# USB_Type-C_Test.net
KiCad netlist of a schematic drawn in EAGLE
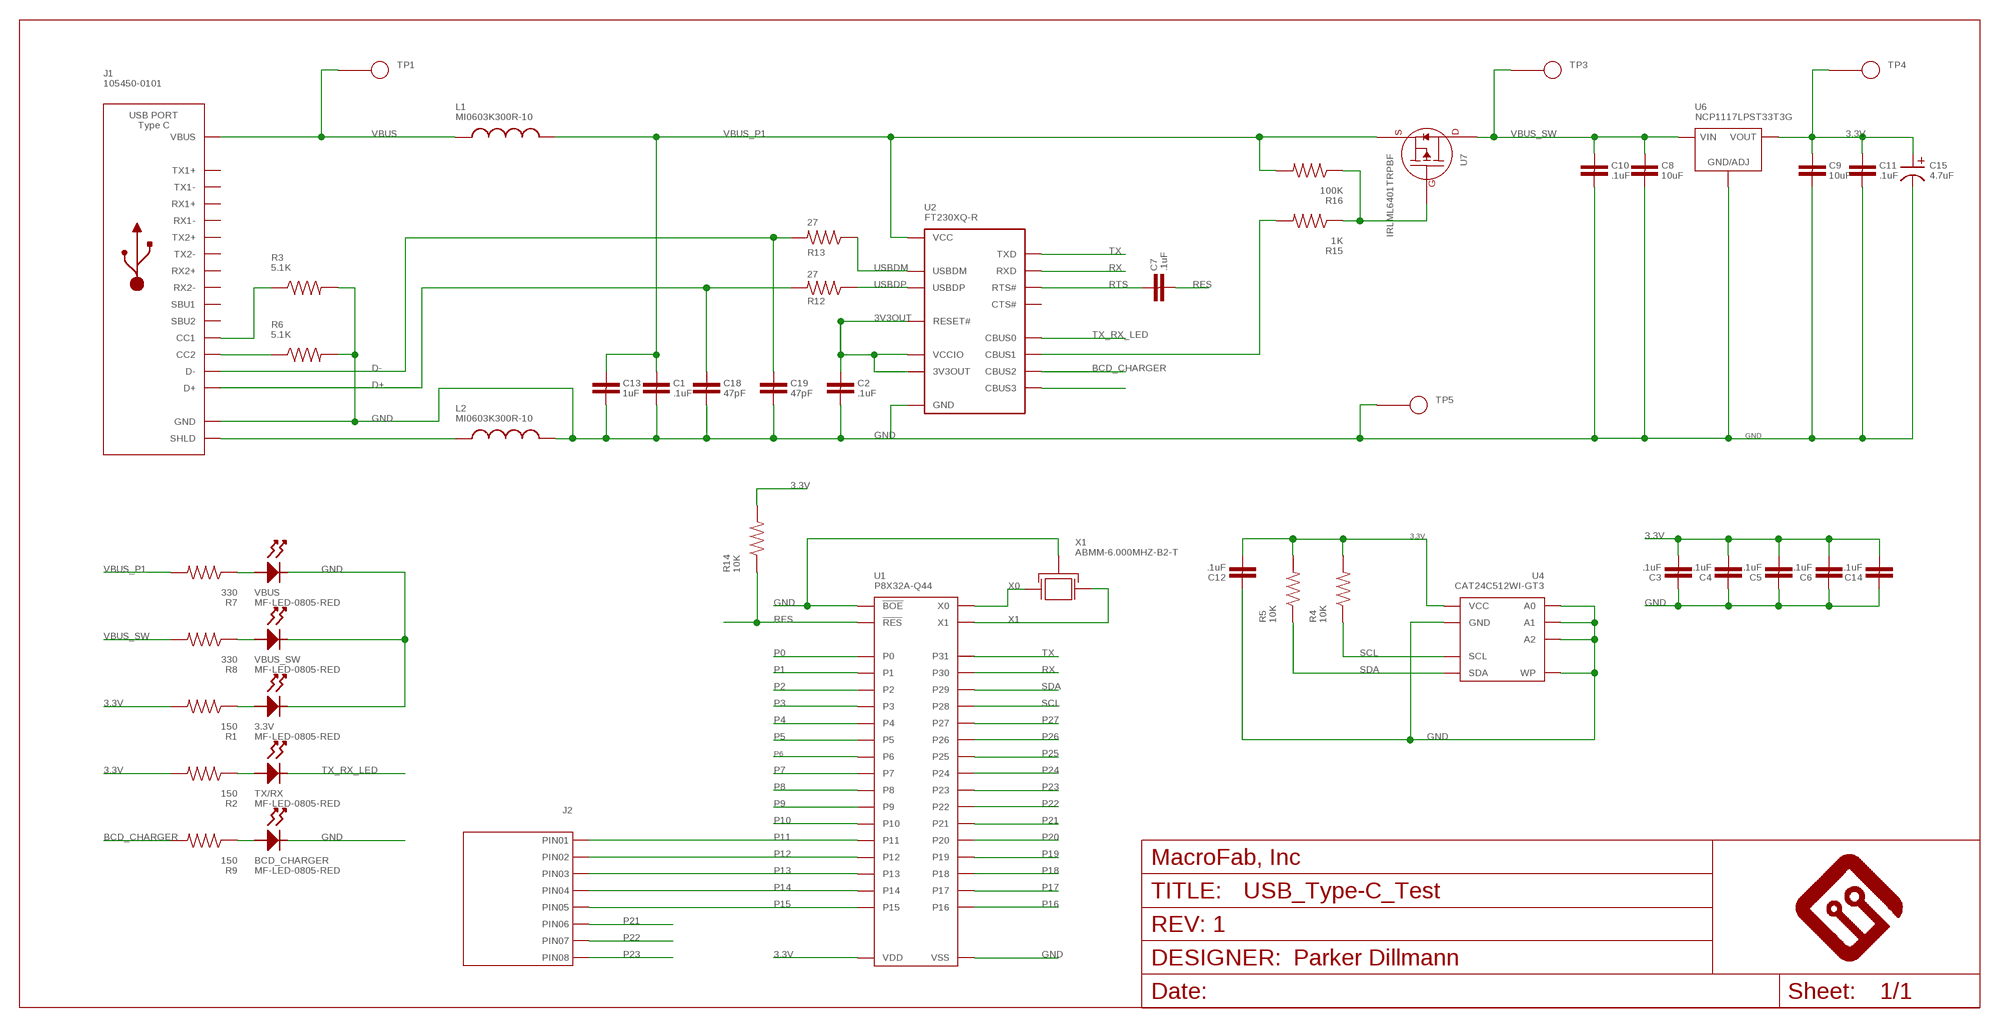
[diagram p0: schematic, sheet 1]

(export (version "E")
  (design (tool "Eeschema 10.0.6"))
  (components
    (comp (ref "3.3V")
      (value "MF-LED-0805-RED")
      (footprint "eagle-import:LED_0805")
      (libsource (lib "eagle-import") (part "LED_SINGLE_0805"))
    )
    (comp (ref "BCD_CHARGER")
      (value "MF-LED-0805-RED")
      (footprint "eagle-import:LED_0805")
      (libsource (lib "eagle-import") (part "LED_SINGLE_0805"))
    )
    (comp (ref "C1")
      (value ".1uF")
      (footprint "eagle-import:0603")
      (libsource (lib "eagle-import") (part "CAPACITOR_NON_POLAR_0603"))
    )
    (comp (ref "C2")
      (value ".1uF")
      (footprint "eagle-import:0603")
      (libsource (lib "eagle-import") (part "CAPACITOR_NON_POLAR_0603"))
    )
    (comp (ref "C3")
      (value ".1uF")
      (footprint "eagle-import:0603")
      (libsource (lib "eagle-import") (part "CAPACITOR_NON_POLAR_0603"))
    )
    (comp (ref "C4")
      (value ".1uF")
      (footprint "eagle-import:0603")
      (libsource (lib "eagle-import") (part "CAPACITOR_NON_POLAR_0603"))
    )
    (comp (ref "C5")
      (value ".1uF")
      (footprint "eagle-import:0603")
      (libsource (lib "eagle-import") (part "CAPACITOR_NON_POLAR_0603"))
    )
    (comp (ref "C6")
      (value ".1uF")
      (footprint "eagle-import:0603")
      (libsource (lib "eagle-import") (part "CAPACITOR_NON_POLAR_0603"))
    )
    (comp (ref "C7")
      (value ".1uF")
      (footprint "eagle-import:0603")
      (libsource (lib "eagle-import") (part "CAPACITOR_NON_POLAR_0603"))
    )
    (comp (ref "C8")
      (value "10uF")
      (footprint "eagle-import:1206")
      (libsource (lib "eagle-import") (part "CAPACITOR_NON_POLAR_1206"))
    )
    (comp (ref "C9")
      (value "10uF")
      (footprint "eagle-import:1206")
      (libsource (lib "eagle-import") (part "CAPACITOR_NON_POLAR_1206"))
    )
    (comp (ref "C10")
      (value ".1uF")
      (footprint "eagle-import:0603")
      (libsource (lib "eagle-import") (part "CAPACITOR_NON_POLAR_0603"))
    )
    (comp (ref "C11")
      (value ".1uF")
      (footprint "eagle-import:0603")
      (libsource (lib "eagle-import") (part "CAPACITOR_NON_POLAR_0603"))
    )
    (comp (ref "C12")
      (value ".1uF")
      (footprint "eagle-import:0603")
      (libsource (lib "eagle-import") (part "CAPACITOR_NON_POLAR_0603"))
    )
    (comp (ref "C13")
      (value "1uF")
      (footprint "eagle-import:0603")
      (libsource (lib "eagle-import") (part "CAPACITOR_NON_POLAR_0603"))
    )
    (comp (ref "C14")
      (value ".1uF")
      (footprint "eagle-import:0603")
      (libsource (lib "eagle-import") (part "CAPACITOR_NON_POLAR_0603"))
    )
    (comp (ref "C15")
      (value "4.7uF")
      (footprint "eagle-import:5MM_CAP_SMD")
      (libsource (lib "eagle-import") (part "CAPACITOR_POLARIZED_5MM_SMD"))
    )
    (comp (ref "C18")
      (value "47pF")
      (footprint "eagle-import:0603")
      (libsource (lib "eagle-import") (part "CAPACITOR_NON_POLAR_0603"))
    )
    (comp (ref "C19")
      (value "47pF")
      (footprint "eagle-import:0603")
      (libsource (lib "eagle-import") (part "CAPACITOR_NON_POLAR_0603"))
    )
    (comp (ref "FRAME1")
      (value "MF_FRAMEDEFAULT")
      (footprint "eagle-import:MF_FRAME_DEFAULT")
      (fields
        (field (name "HOUSEPART") "0")
        (field (name "DNAME") "Parker Dillmann")
        (field (name "REVNUM") "REV: 1")
      )
      (libsource (lib "eagle-import") (part "MF_FRAMEDEFAULT"))
    )
    (comp (ref "J1")
      (value "105450-0101")
      (footprint "eagle-import:105450-0101")
      (fields (field (name "MPN") "105450-0101"))
      (libsource (lib "eagle-import") (part "USB_TYPE-C_105450-0101"))
    )
    (comp (ref "J2")
      (value "CON_01X08_2.54MM_PIN_HEADER")
      (footprint "eagle-import:2.54MM_01X08_PIN_HEADER")
      (libsource (lib "eagle-import") (part "CON_01X08_2.54MM_PIN_HEADER"))
    )
    (comp (ref "L1")
      (value "MI0603K300R-10")
      (footprint "eagle-import:0603")
      (libsource (lib "eagle-import") (part "INDUCTOR_0603"))
    )
    (comp (ref "L2")
      (value "MI0603K300R-10")
      (footprint "eagle-import:0603")
      (libsource (lib "eagle-import") (part "INDUCTOR_0603"))
    )
    (comp (ref "R1")
      (value "150")
      (footprint "eagle-import:0603")
      (libsource (lib "eagle-import") (part "RESISTOR_0603"))
    )
    (comp (ref "R2")
      (value "150")
      (footprint "eagle-import:0603")
      (libsource (lib "eagle-import") (part "RESISTOR_0603"))
    )
    (comp (ref "R3")
      (value "5.1K")
      (footprint "eagle-import:0603")
      (libsource (lib "eagle-import") (part "RESISTOR_0603"))
    )
    (comp (ref "R4")
      (value "10K")
      (footprint "eagle-import:0603")
      (libsource (lib "eagle-import") (part "RESISTOR_0603"))
    )
    (comp (ref "R5")
      (value "10K")
      (footprint "eagle-import:0603")
      (libsource (lib "eagle-import") (part "RESISTOR_0603"))
    )
    (comp (ref "R6")
      (value "5.1K")
      (footprint "eagle-import:0603")
      (libsource (lib "eagle-import") (part "RESISTOR_0603"))
    )
    (comp (ref "R7")
      (value "330")
      (footprint "eagle-import:0603")
      (libsource (lib "eagle-import") (part "RESISTOR_0603"))
    )
    (comp (ref "R8")
      (value "330")
      (footprint "eagle-import:0603")
      (libsource (lib "eagle-import") (part "RESISTOR_0603"))
    )
    (comp (ref "R9")
      (value "150")
      (footprint "eagle-import:0603")
      (libsource (lib "eagle-import") (part "RESISTOR_0603"))
    )
    (comp (ref "R12")
      (value "27")
      (footprint "eagle-import:0603")
      (libsource (lib "eagle-import") (part "RESISTOR_0603"))
    )
    (comp (ref "R13")
      (value "27")
      (footprint "eagle-import:0603")
      (libsource (lib "eagle-import") (part "RESISTOR_0603"))
    )
    (comp (ref "R14")
      (value "10K")
      (footprint "eagle-import:0603")
      (libsource (lib "eagle-import") (part "RESISTOR_0603"))
    )
    (comp (ref "R15")
      (value "1K")
      (footprint "eagle-import:0603")
      (libsource (lib "eagle-import") (part "RESISTOR_0603"))
    )
    (comp (ref "R16")
      (value "100K")
      (footprint "eagle-import:0603")
      (libsource (lib "eagle-import") (part "RESISTOR_0603"))
    )
    (comp (ref "TP1")
      (value "TEST_POINT_SINGLE_KEYSTONE_5115-5119")
      (footprint "eagle-import:KEYSTONE_5115-5119")
      (libsource (lib "eagle-import") (part "TEST_POINT_SINGLE_KEYSTONE_5115-5119"))
    )
    (comp (ref "TP3")
      (value "TEST_POINT_SINGLE_KEYSTONE_5115-5119")
      (footprint "eagle-import:KEYSTONE_5115-5119")
      (libsource (lib "eagle-import") (part "TEST_POINT_SINGLE_KEYSTONE_5115-5119"))
    )
    (comp (ref "TP4")
      (value "TEST_POINT_SINGLE_KEYSTONE_5115-5119")
      (footprint "eagle-import:KEYSTONE_5115-5119")
      (libsource (lib "eagle-import") (part "TEST_POINT_SINGLE_KEYSTONE_5115-5119"))
    )
    (comp (ref "TP5")
      (value "TEST_POINT_SINGLE_KEYSTONE_5115-5119")
      (footprint "eagle-import:KEYSTONE_5115-5119")
      (libsource (lib "eagle-import") (part "TEST_POINT_SINGLE_KEYSTONE_5115-5119"))
    )
    (comp (ref "TX/RX")
      (value "MF-LED-0805-RED")
      (footprint "eagle-import:LED_0805")
      (libsource (lib "eagle-import") (part "LED_SINGLE_0805"))
    )
    (comp (ref "U1")
      (value "P8X32A-Q44")
      (footprint "eagle-import:P8X32A_LQFP-44")
      (libsource (lib "eagle-import") (part "P8X32A-Q44"))
    )
    (comp (ref "U2")
      (value "FT230XQ-R")
      (footprint "eagle-import:FT230X_QFN-16")
      (libsource (lib "eagle-import") (part "FT230XQ"))
    )
    (comp (ref "U4")
      (value "CAT24C512WI-GT3")
      (footprint "eagle-import:SOIC-8_W")
      (libsource (lib "eagle-import") (part "EEPROM_I2CSOIC-8_W"))
    )
    (comp (ref "U6")
      (value "NCP1117LPST33T3G")
      (footprint "eagle-import:SOT-223-3")
      (fields (field (name "HOUSEPART") "NO"))
      (libsource (lib "eagle-import") (part "NCP1117LPST33T3G"))
    )
    (comp (ref "U7")
      (value "IRLML6401TRPBF")
      (footprint "eagle-import:SOT-23-3")
      (libsource (lib "eagle-import") (part "MOSFET_P-CHANNEL_SINGLE_SOT-23"))
    )
    (comp (ref "VBUS")
      (value "MF-LED-0805-RED")
      (footprint "eagle-import:LED_0805")
      (libsource (lib "eagle-import") (part "LED_SINGLE_0805"))
    )
    (comp (ref "VBUS_SW")
      (value "MF-LED-0805-RED")
      (footprint "eagle-import:LED_0805")
      (libsource (lib "eagle-import") (part "LED_SINGLE_0805"))
    )
    (comp (ref "X1")
      (value "ABMM-6.000MHZ-B2-T")
      (footprint "eagle-import:7MMX5MM")
      (fields (field (name "HOUSEPART") "NO"))
      (libsource (lib "eagle-import") (part "CYRSTAL_GND_ABMM"))
    )
  )
  (nets
    (net (code "1") (name "/3.3V") (class "Default")
      (node (ref "C11") (pin "1") (pinfunction "1_1") (pintype "passive"))
      (node (ref "C12") (pin "2") (pinfunction "2_2") (pintype "passive"))
      (node (ref "C14") (pin "2") (pinfunction "2_2") (pintype "passive"))
      (node (ref "C15") (pin "P") (pinfunction "POS_P") (pintype "bidirectional"))
      (node (ref "C3") (pin "2") (pinfunction "2_2") (pintype "passive"))
      (node (ref "C4") (pin "2") (pinfunction "2_2") (pintype "passive"))
      (node (ref "C5") (pin "2") (pinfunction "2_2") (pintype "passive"))
      (node (ref "C6") (pin "2") (pinfunction "2_2") (pintype "passive"))
      (node (ref "C9") (pin "1") (pinfunction "1_1") (pintype "passive"))
      (node (ref "R1") (pin "2") (pinfunction "2_2") (pintype "passive"))
      (node (ref "R14") (pin "2") (pinfunction "2_2") (pintype "passive"))
      (node (ref "R2") (pin "2") (pinfunction "2_2") (pintype "passive"))
      (node (ref "R4") (pin "2") (pinfunction "2_2") (pintype "passive"))
      (node (ref "R5") (pin "2") (pinfunction "2_2") (pintype "passive"))
      (node (ref "TP4") (pin "P$1") (pinfunction "P$1_P$1") (pintype "bidirectional"))
      (node (ref "U1") (pin "18") (pinfunction "VDD_18") (pintype "bidirectional"))
      (node (ref "U1") (pin "30") (pinfunction "VDD_30") (pintype "bidirectional"))
      (node (ref "U1") (pin "40") (pinfunction "VDD_40") (pintype "bidirectional"))
      (node (ref "U1") (pin "8") (pinfunction "VDD_8") (pintype "bidirectional"))
      (node (ref "U4") (pin "8") (pinfunction "VCC_8") (pintype "bidirectional"))
      (node (ref "U6") (pin "P$1") (pinfunction "VOUT_P$1") (pintype "bidirectional"))
      (node (ref "U6") (pin "P$3") (pinfunction "VOUT_P$3") (pintype "bidirectional"))
    )
    (net (code "2") (name "/3V3OUT") (class "Default")
      (node (ref "C2") (pin "1") (pinfunction "1_1") (pintype "passive"))
      (node (ref "U2") (pin "1") (pinfunction "VCCIO_1") (pintype "bidirectional"))
      (node (ref "U2") (pin "8") (pinfunction "3V3OUT_8") (pintype "bidirectional"))
      (node (ref "U2") (pin "9") (pinfunction "RESET#_9") (pintype "bidirectional"))
    )
    (net (code "3") (name "/BCD_CHARGER") (class "Default")
      (node (ref "R9") (pin "2") (pinfunction "2_2") (pintype "passive"))
      (node (ref "U2") (pin "5") (pinfunction "CBUS2_5") (pintype "bidirectional"))
    )
    (net (code "4") (name "/D+") (class "Default")
      (node (ref "C18") (pin "1") (pinfunction "1_1") (pintype "passive"))
      (node (ref "J1") (pin "A6") (pinfunction "D+_A6") (pintype "bidirectional"))
      (node (ref "J1") (pin "B6") (pinfunction "D+_B6") (pintype "bidirectional"))
      (node (ref "R12") (pin "2") (pinfunction "2_2") (pintype "passive"))
    )
    (net (code "5") (name "/D-") (class "Default")
      (node (ref "C19") (pin "1") (pinfunction "1_1") (pintype "passive"))
      (node (ref "J1") (pin "A7") (pinfunction "D-_A7") (pintype "bidirectional"))
      (node (ref "J1") (pin "B7") (pinfunction "D-_B7") (pintype "bidirectional"))
      (node (ref "R13") (pin "2") (pinfunction "2_2") (pintype "passive"))
    )
    (net (code "6") (name "/GND") (class "Default")
      (node (ref "3.3V") (pin "CATHODE") (pinfunction "CATHODE_CATHODE") (pintype "bidirectional"))
      (node (ref "BCD_CHARGER") (pin "CATHODE") (pinfunction "CATHODE_CATHODE") (pintype "bidirectional"))
      (node (ref "C1") (pin "2") (pinfunction "2_2") (pintype "passive"))
      (node (ref "C10") (pin "2") (pinfunction "2_2") (pintype "passive"))
      (node (ref "C11") (pin "2") (pinfunction "2_2") (pintype "passive"))
      (node (ref "C12") (pin "1") (pinfunction "1_1") (pintype "passive"))
      (node (ref "C13") (pin "2") (pinfunction "2_2") (pintype "passive"))
      (node (ref "C14") (pin "1") (pinfunction "1_1") (pintype "passive"))
      (node (ref "C15") (pin "N") (pinfunction "NEG_N") (pintype "bidirectional"))
      (node (ref "C18") (pin "2") (pinfunction "2_2") (pintype "passive"))
      (node (ref "C19") (pin "2") (pinfunction "2_2") (pintype "passive"))
      (node (ref "C2") (pin "2") (pinfunction "2_2") (pintype "passive"))
      (node (ref "C3") (pin "1") (pinfunction "1_1") (pintype "passive"))
      (node (ref "C4") (pin "1") (pinfunction "1_1") (pintype "passive"))
      (node (ref "C5") (pin "1") (pinfunction "1_1") (pintype "passive"))
      (node (ref "C6") (pin "1") (pinfunction "1_1") (pintype "passive"))
      (node (ref "C8") (pin "2") (pinfunction "2_2") (pintype "passive"))
      (node (ref "C9") (pin "2") (pinfunction "2_2") (pintype "passive"))
      (node (ref "J1") (pin "A1") (pinfunction "GND_A1") (pintype "bidirectional"))
      (node (ref "J1") (pin "A12") (pinfunction "GND_A12") (pintype "bidirectional"))
      (node (ref "J1") (pin "B1") (pinfunction "GND_B1") (pintype "bidirectional"))
      (node (ref "J1") (pin "B12") (pinfunction "GND_B12") (pintype "bidirectional"))
      (node (ref "L2") (pin "2") (pinfunction "P$2_2") (pintype "bidirectional"))
      (node (ref "R3") (pin "2") (pinfunction "2_2") (pintype "passive"))
      (node (ref "R6") (pin "2") (pinfunction "2_2") (pintype "passive"))
      (node (ref "TP5") (pin "P$1") (pinfunction "P$1_P$1") (pintype "bidirectional"))
      (node (ref "U1") (pin "17") (pinfunction "VSS_17") (pintype "bidirectional"))
      (node (ref "U1") (pin "27") (pinfunction "VSS_27") (pintype "bidirectional"))
      (node (ref "U1") (pin "39") (pinfunction "VSS_39") (pintype "bidirectional"))
      (node (ref "U1") (pin "5") (pinfunction "VSS_5") (pintype "bidirectional"))
      (node (ref "U1") (pin "6") (pinfunction "~{BOE}_6") (pintype "bidirectional"))
      (node (ref "U2") (pin "13") (pinfunction "GND_13") (pintype "bidirectional"))
      (node (ref "U2") (pin "3") (pinfunction "GND_3") (pintype "bidirectional"))
      (node (ref "U2") (pin "PAD") (pinfunction "GND_PAD") (pintype "bidirectional"))
      (node (ref "U4") (pin "1") (pinfunction "A0_1") (pintype "bidirectional"))
      (node (ref "U4") (pin "2") (pinfunction "A1_2") (pintype "bidirectional"))
      (node (ref "U4") (pin "3") (pinfunction "A2_3") (pintype "bidirectional"))
      (node (ref "U4") (pin "4") (pinfunction "GND_4") (pintype "bidirectional"))
      (node (ref "U4") (pin "7") (pinfunction "WP_7") (pintype "bidirectional"))
      (node (ref "U6") (pin "P$2") (pinfunction "GND/ADJ_P$2") (pintype "bidirectional"))
      (node (ref "VBUS") (pin "CATHODE") (pinfunction "CATHODE_CATHODE") (pintype "bidirectional"))
      (node (ref "VBUS_SW") (pin "CATHODE") (pinfunction "CATHODE_CATHODE") (pintype "bidirectional"))
      (node (ref "X1") (pin "P$2") (pinfunction "GND_P$2") (pintype "bidirectional"))
      (node (ref "X1") (pin "P$4") (pinfunction "GND_P$4") (pintype "bidirectional"))
    )
    (net (code "7") (name "/P0") (class "Default")
      (node (ref "U1") (pin "41") (pinfunction "P0_41") (pintype "bidirectional"))
    )
    (net (code "8") (name "/P1") (class "Default")
      (node (ref "U1") (pin "42") (pinfunction "P1_42") (pintype "bidirectional"))
    )
    (net (code "9") (name "/P2") (class "Default")
      (node (ref "U1") (pin "43") (pinfunction "P2_43") (pintype "bidirectional"))
    )
    (net (code "10") (name "/P3") (class "Default")
      (node (ref "U1") (pin "44") (pinfunction "P3_44") (pintype "bidirectional"))
    )
    (net (code "11") (name "/P4") (class "Default")
      (node (ref "U1") (pin "1") (pinfunction "P4_1") (pintype "bidirectional"))
    )
    (net (code "12") (name "/P5") (class "Default")
      (node (ref "U1") (pin "2") (pinfunction "P5_2") (pintype "bidirectional"))
    )
    (net (code "13") (name "/P6") (class "Default")
      (node (ref "U1") (pin "3") (pinfunction "P6_3") (pintype "bidirectional"))
    )
    (net (code "14") (name "/P7") (class "Default")
      (node (ref "U1") (pin "4") (pinfunction "P7_4") (pintype "bidirectional"))
    )
    (net (code "15") (name "/P8") (class "Default")
      (node (ref "U1") (pin "9") (pinfunction "P8_9") (pintype "bidirectional"))
    )
    (net (code "16") (name "/P9") (class "Default")
      (node (ref "U1") (pin "10") (pinfunction "P9_10") (pintype "bidirectional"))
    )
    (net (code "17") (name "/P10") (class "Default")
      (node (ref "U1") (pin "11") (pinfunction "P10_11") (pintype "bidirectional"))
    )
    (net (code "18") (name "/P11") (class "Default")
      (node (ref "J2") (pin "1") (pinfunction "1_1") (pintype "bidirectional"))
      (node (ref "U1") (pin "12") (pinfunction "P11_12") (pintype "bidirectional"))
    )
    (net (code "19") (name "/P12") (class "Default")
      (node (ref "J2") (pin "2") (pinfunction "2_2") (pintype "bidirectional"))
      (node (ref "U1") (pin "13") (pinfunction "P12_13") (pintype "bidirectional"))
    )
    (net (code "20") (name "/P13") (class "Default")
      (node (ref "J2") (pin "3") (pinfunction "3_3") (pintype "bidirectional"))
      (node (ref "U1") (pin "14") (pinfunction "P13_14") (pintype "bidirectional"))
    )
    (net (code "21") (name "/P14") (class "Default")
      (node (ref "J2") (pin "4") (pinfunction "4_4") (pintype "bidirectional"))
      (node (ref "U1") (pin "15") (pinfunction "P14_15") (pintype "bidirectional"))
    )
    (net (code "22") (name "/P15") (class "Default")
      (node (ref "J2") (pin "5") (pinfunction "5_5") (pintype "bidirectional"))
      (node (ref "U1") (pin "16") (pinfunction "P15_16") (pintype "bidirectional"))
    )
    (net (code "23") (name "/P16") (class "Default")
      (node (ref "U1") (pin "19") (pinfunction "P16_19") (pintype "bidirectional"))
    )
    (net (code "24") (name "/P17") (class "Default")
      (node (ref "U1") (pin "20") (pinfunction "P17_20") (pintype "bidirectional"))
    )
    (net (code "25") (name "/P18") (class "Default")
      (node (ref "U1") (pin "21") (pinfunction "P18_21") (pintype "bidirectional"))
    )
    (net (code "26") (name "/P19") (class "Default")
      (node (ref "U1") (pin "22") (pinfunction "P19_22") (pintype "bidirectional"))
    )
    (net (code "27") (name "/P20") (class "Default")
      (node (ref "U1") (pin "23") (pinfunction "P20_23") (pintype "bidirectional"))
    )
    (net (code "28") (name "/P21") (class "Default")
      (node (ref "J2") (pin "6") (pinfunction "6_6") (pintype "bidirectional"))
      (node (ref "U1") (pin "24") (pinfunction "P21_24") (pintype "bidirectional"))
    )
    (net (code "29") (name "/P22") (class "Default")
      (node (ref "J2") (pin "7") (pinfunction "7_7") (pintype "bidirectional"))
      (node (ref "U1") (pin "25") (pinfunction "P22_25") (pintype "bidirectional"))
    )
    (net (code "30") (name "/P23") (class "Default")
      (node (ref "J2") (pin "8") (pinfunction "8_8") (pintype "bidirectional"))
      (node (ref "U1") (pin "26") (pinfunction "P23_26") (pintype "bidirectional"))
    )
    (net (code "31") (name "/P24") (class "Default")
      (node (ref "U1") (pin "31") (pinfunction "P24_31") (pintype "bidirectional"))
    )
    (net (code "32") (name "/P25") (class "Default")
      (node (ref "U1") (pin "32") (pinfunction "P25_32") (pintype "bidirectional"))
    )
    (net (code "33") (name "/P26") (class "Default")
      (node (ref "U1") (pin "33") (pinfunction "P26_33") (pintype "bidirectional"))
    )
    (net (code "34") (name "/P27") (class "Default")
      (node (ref "U1") (pin "34") (pinfunction "P27_34") (pintype "bidirectional"))
    )
    (net (code "35") (name "/RES") (class "Default")
      (node (ref "C7") (pin "2") (pinfunction "2_2") (pintype "passive"))
      (node (ref "R14") (pin "1") (pinfunction "1_1") (pintype "passive"))
      (node (ref "U1") (pin "7") (pinfunction "~{RES}_7") (pintype "bidirectional"))
    )
    (net (code "36") (name "/RTS") (class "Default")
      (node (ref "C7") (pin "1") (pinfunction "1_1") (pintype "passive"))
      (node (ref "U2") (pin "16") (pinfunction "RTS#_16") (pintype "bidirectional"))
    )
    (net (code "37") (name "/RX") (class "Default")
      (node (ref "U1") (pin "37") (pinfunction "P30_37") (pintype "bidirectional"))
      (node (ref "U2") (pin "2") (pinfunction "RXD_2") (pintype "bidirectional"))
    )
    (net (code "38") (name "/SCL") (class "Default")
      (node (ref "R4") (pin "1") (pinfunction "1_1") (pintype "passive"))
      (node (ref "U1") (pin "35") (pinfunction "P28_35") (pintype "bidirectional"))
      (node (ref "U4") (pin "6") (pinfunction "SCL_6") (pintype "bidirectional"))
    )
    (net (code "39") (name "/SDA") (class "Default")
      (node (ref "R5") (pin "1") (pinfunction "1_1") (pintype "passive"))
      (node (ref "U1") (pin "36") (pinfunction "P29_36") (pintype "bidirectional"))
      (node (ref "U4") (pin "5") (pinfunction "SDA_5") (pintype "bidirectional"))
    )
    (net (code "40") (name "/TX") (class "Default")
      (node (ref "U1") (pin "38") (pinfunction "P31_38") (pintype "bidirectional"))
      (node (ref "U2") (pin "15") (pinfunction "TXD_15") (pintype "bidirectional"))
    )
    (net (code "41") (name "/TX_RX_LED") (class "Default")
      (node (ref "TX/RX") (pin "CATHODE") (pinfunction "CATHODE_CATHODE") (pintype "bidirectional"))
      (node (ref "U2") (pin "12") (pinfunction "CBUS0_12") (pintype "bidirectional"))
    )
    (net (code "42") (name "/USBDM") (class "Default")
      (node (ref "R13") (pin "1") (pinfunction "1_1") (pintype "passive"))
      (node (ref "U2") (pin "7") (pinfunction "USBDM_7") (pintype "bidirectional"))
    )
    (net (code "43") (name "/USBDP") (class "Default")
      (node (ref "R12") (pin "1") (pinfunction "1_1") (pintype "passive"))
      (node (ref "U2") (pin "6") (pinfunction "USBDP_6") (pintype "bidirectional"))
    )
    (net (code "44") (name "/VBUS") (class "Default")
      (node (ref "J1") (pin "A4") (pinfunction "VBUS_A4") (pintype "bidirectional"))
      (node (ref "J1") (pin "A9") (pinfunction "VBUS_A9") (pintype "bidirectional"))
      (node (ref "J1") (pin "B4") (pinfunction "VBUS_B4") (pintype "bidirectional"))
      (node (ref "J1") (pin "B9") (pinfunction "VBUS_B9") (pintype "bidirectional"))
      (node (ref "L1") (pin "1") (pinfunction "P$1_1") (pintype "bidirectional"))
      (node (ref "TP1") (pin "P$1") (pinfunction "P$1_P$1") (pintype "bidirectional"))
    )
    (net (code "45") (name "/VBUS_P1") (class "Default")
      (node (ref "C1") (pin "1") (pinfunction "1_1") (pintype "passive"))
      (node (ref "C13") (pin "1") (pinfunction "1_1") (pintype "passive"))
      (node (ref "L1") (pin "2") (pinfunction "P$2_2") (pintype "bidirectional"))
      (node (ref "R16") (pin "2") (pinfunction "2_2") (pintype "passive"))
      (node (ref "R7") (pin "2") (pinfunction "2_2") (pintype "passive"))
      (node (ref "U2") (pin "10") (pinfunction "VCC_10") (pintype "bidirectional"))
      (node (ref "U7") (pin "2") (pinfunction "SOURCE_2") (pintype "bidirectional"))
    )
    (net (code "46") (name "/VBUS_SW") (class "Default")
      (node (ref "C10") (pin "1") (pinfunction "1_1") (pintype "passive"))
      (node (ref "C8") (pin "1") (pinfunction "1_1") (pintype "passive"))
      (node (ref "R8") (pin "2") (pinfunction "2_2") (pintype "passive"))
      (node (ref "TP3") (pin "P$1") (pinfunction "P$1_P$1") (pintype "bidirectional"))
      (node (ref "U6") (pin "P$4") (pinfunction "VIN_P$4") (pintype "bidirectional"))
      (node (ref "U7") (pin "3") (pinfunction "DRAIN_3") (pintype "bidirectional"))
    )
    (net (code "47") (name "/X0") (class "Default")
      (node (ref "U1") (pin "29") (pinfunction "X0_29") (pintype "bidirectional"))
      (node (ref "X1") (pin "P$3") (pinfunction "X1_P$3") (pintype "bidirectional"))
    )
    (net (code "48") (name "/X1") (class "Default")
      (node (ref "U1") (pin "28") (pinfunction "X1_28") (pintype "bidirectional"))
      (node (ref "X1") (pin "P$1") (pinfunction "X0_P$1") (pintype "bidirectional"))
    )
    (net (code "49") (name "Net-(3.3V-PadANODE)") (class "Default")
      (node (ref "3.3V") (pin "ANODE") (pinfunction "ANODE_ANODE") (pintype "bidirectional"))
      (node (ref "R1") (pin "1") (pinfunction "1_1") (pintype "passive"))
    )
    (net (code "50") (name "Net-(BCD_CHARGER-PadANODE)") (class "Default")
      (node (ref "BCD_CHARGER") (pin "ANODE") (pinfunction "ANODE_ANODE") (pintype "bidirectional"))
      (node (ref "R9") (pin "1") (pinfunction "1_1") (pintype "passive"))
    )
    (net (code "51") (name "Net-(J1-CC1)") (class "Default")
      (node (ref "J1") (pin "A5") (pinfunction "CC1_A5") (pintype "bidirectional"))
      (node (ref "R3") (pin "1") (pinfunction "1_1") (pintype "passive"))
    )
    (net (code "52") (name "Net-(J1-CC2)") (class "Default")
      (node (ref "J1") (pin "B5") (pinfunction "CC2_B5") (pintype "bidirectional"))
      (node (ref "R6") (pin "1") (pinfunction "1_1") (pintype "passive"))
    )
    (net (code "53") (name "Net-(L2-P$1)") (class "Default")
      (node (ref "J1") (pin "S_T1") (pinfunction "SHLD_S_T1") (pintype "bidirectional"))
      (node (ref "J1") (pin "S_T2") (pinfunction "SHLD_S_T2") (pintype "bidirectional"))
      (node (ref "J1") (pin "S_T3") (pinfunction "SHLD_S_T3") (pintype "bidirectional"))
      (node (ref "J1") (pin "S_T4") (pinfunction "SHLD_S_T4") (pintype "bidirectional"))
      (node (ref "L2") (pin "1") (pinfunction "P$1_1") (pintype "bidirectional"))
    )
    (net (code "54") (name "Net-(R2-Pad1)") (class "Default")
      (node (ref "R2") (pin "1") (pinfunction "1_1") (pintype "passive"))
      (node (ref "TX/RX") (pin "ANODE") (pinfunction "ANODE_ANODE") (pintype "bidirectional"))
    )
    (net (code "55") (name "Net-(R7-Pad1)") (class "Default")
      (node (ref "R7") (pin "1") (pinfunction "1_1") (pintype "passive"))
      (node (ref "VBUS") (pin "ANODE") (pinfunction "ANODE_ANODE") (pintype "bidirectional"))
    )
    (net (code "56") (name "Net-(R8-Pad1)") (class "Default")
      (node (ref "R8") (pin "1") (pinfunction "1_1") (pintype "passive"))
      (node (ref "VBUS_SW") (pin "ANODE") (pinfunction "ANODE_ANODE") (pintype "bidirectional"))
    )
    (net (code "57") (name "Net-(U2-CBUS1)") (class "Default")
      (node (ref "R15") (pin "2") (pinfunction "2_2") (pintype "passive"))
      (node (ref "U2") (pin "11") (pinfunction "CBUS1_11") (pintype "bidirectional"))
    )
    (net (code "58") (name "Net-(U7-GATE)") (class "Default")
      (node (ref "R15") (pin "1") (pinfunction "1_1") (pintype "passive"))
      (node (ref "R16") (pin "1") (pinfunction "1_1") (pintype "passive"))
      (node (ref "U7") (pin "1") (pinfunction "GATE_1") (pintype "bidirectional"))
    )
    (net (code "59") (name "unconnected-(J1-RX1+-PadB11)") (class "Default")
      (node (ref "J1") (pin "B11") (pinfunction "RX1+_B11") (pintype "bidirectional"))
    )
    (net (code "60") (name "unconnected-(J1-RX1--PadB10)") (class "Default")
      (node (ref "J1") (pin "B10") (pinfunction "RX1-_B10") (pintype "bidirectional"))
    )
    (net (code "61") (name "unconnected-(J1-RX2+-PadA11)") (class "Default")
      (node (ref "J1") (pin "A11") (pinfunction "RX2+_A11") (pintype "bidirectional"))
    )
    (net (code "62") (name "unconnected-(J1-RX2--PadA10)") (class "Default")
      (node (ref "J1") (pin "A10") (pinfunction "RX2-_A10") (pintype "bidirectional"))
    )
    (net (code "63") (name "unconnected-(J1-SBU1-PadA8)") (class "Default")
      (node (ref "J1") (pin "A8") (pinfunction "SBU1_A8") (pintype "bidirectional"))
    )
    (net (code "64") (name "unconnected-(J1-SBU2-PadB8)") (class "Default")
      (node (ref "J1") (pin "B8") (pinfunction "SBU2_B8") (pintype "bidirectional"))
    )
    (net (code "65") (name "unconnected-(J1-TX1+-PadA2)") (class "Default")
      (node (ref "J1") (pin "A2") (pinfunction "TX1+_A2") (pintype "bidirectional"))
    )
    (net (code "66") (name "unconnected-(J1-TX1--PadA3)") (class "Default")
      (node (ref "J1") (pin "A3") (pinfunction "TX1-_A3") (pintype "bidirectional"))
    )
    (net (code "67") (name "unconnected-(J1-TX2+-PadB2)") (class "Default")
      (node (ref "J1") (pin "B2") (pinfunction "TX2+_B2") (pintype "bidirectional"))
    )
    (net (code "68") (name "unconnected-(J1-TX2--PadB3)") (class "Default")
      (node (ref "J1") (pin "B3") (pinfunction "TX2-_B3") (pintype "bidirectional"))
    )
    (net (code "69") (name "unconnected-(U2-CBUS3-Pad14)") (class "Default")
      (node (ref "U2") (pin "14") (pinfunction "CBUS3_14") (pintype "bidirectional"))
    )
    (net (code "70") (name "unconnected-(U2-CTS#-Pad4)") (class "Default")
      (node (ref "U2") (pin "4") (pinfunction "CTS#_4") (pintype "bidirectional"))
    )
  )
)
